# SparkFun_ACS712_Breakout.net
KiCad netlist of a schematic drawn in EAGLE
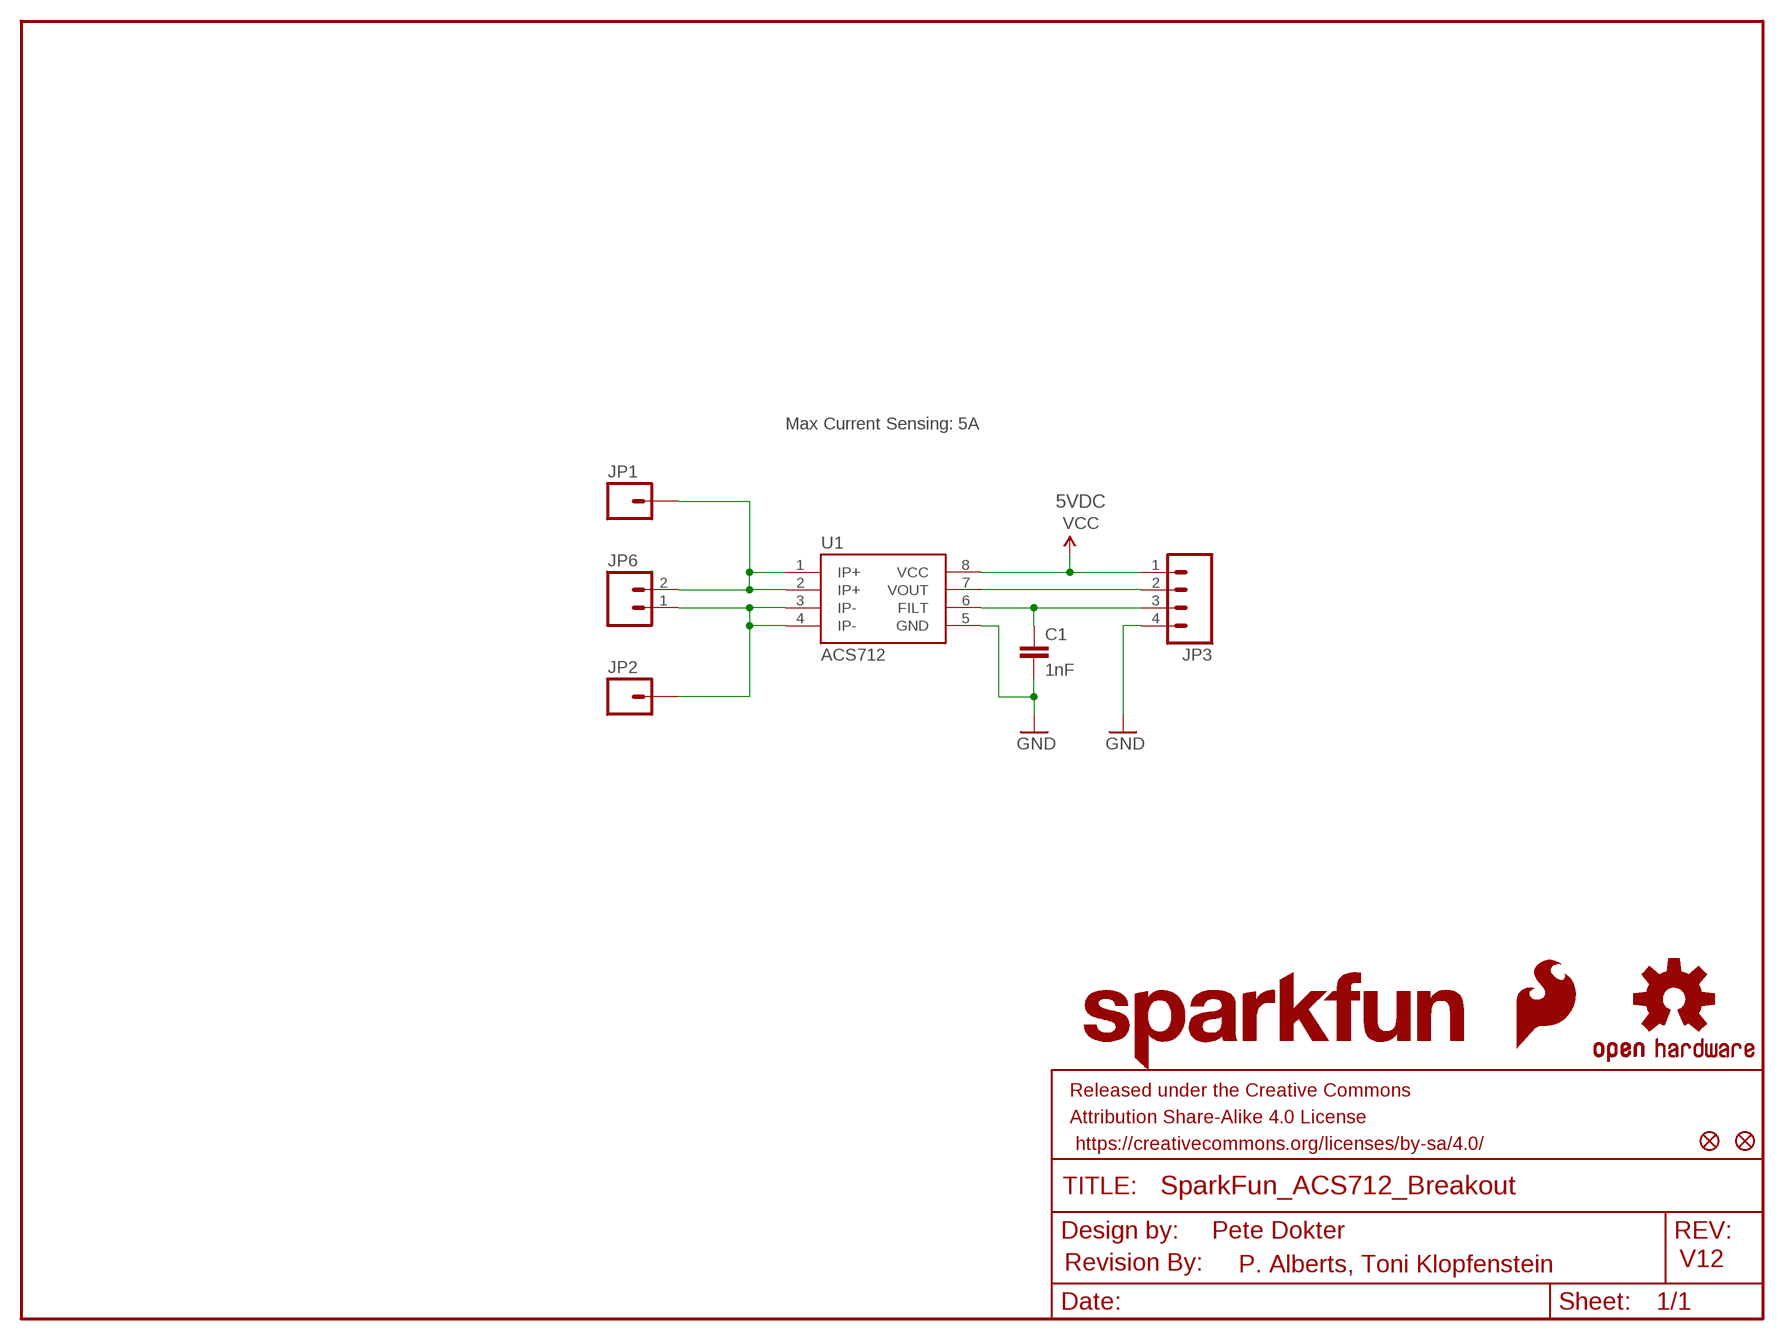
[diagram p0: schematic, sheet 1]

(export (version "E")
  (design (tool "Eeschema 10.0.6"))
  (components
    (comp (ref "C1")
      (value "1nF")
      (footprint "eagle-import:0603-CAP")
      (libsource (lib "eagle-import") (part "1NF/1000PF-50V-10%(0603)"))
    )
    (comp (ref "FRAME1")
      (value "FRAME-LETTER")
      (footprint "eagle-import:CREATIVE_COMMONS")
      (fields (field (name "DESIGNER") "NAME"))
      (libsource (lib "eagle-import") (part "FRAME-LETTER"))
    )
    (comp (ref "JP1")
      (value "M01-SMTSO-256-ET")
      (footprint "eagle-import:SMTSO-256-ET")
      (libsource (lib "eagle-import") (part "M01-SMTSO-256-ET"))
    )
    (comp (ref "JP2")
      (value "M01-SMTSO-256-ET")
      (footprint "eagle-import:SMTSO-256-ET")
      (libsource (lib "eagle-import") (part "M01-SMTSO-256-ET"))
    )
    (comp (ref "JP3")
      (value "M04PTH")
      (footprint "eagle-import:1X04")
      (libsource (lib "eagle-import") (part "M04PTH"))
    )
    (comp (ref "JP4")
      (value "FIDUCIALUFIDUCIAL")
      (footprint "eagle-import:MICRO-FIDUCIAL")
      (libsource (lib "eagle-import") (part "FIDUCIALUFIDUCIAL"))
    )
    (comp (ref "JP5")
      (value "FIDUCIALUFIDUCIAL")
      (footprint "eagle-import:MICRO-FIDUCIAL")
      (libsource (lib "eagle-import") (part "FIDUCIALUFIDUCIAL"))
    )
    (comp (ref "JP6")
      (value "M021X02_NO_SILK")
      (footprint "eagle-import:1X02_NO_SILK")
      (libsource (lib "eagle-import") (part "M021X02_NO_SILK"))
    )
    (comp (ref "LOGO1")
      (value "SFE_LOGO_NAME.1_INCH")
      (footprint "eagle-import:SFE_LOGO_NAME_.1")
      (libsource (lib "eagle-import") (part "SFE_LOGO_NAME.1_INCH"))
    )
    (comp (ref "LOGO2")
      (value "SFE_LOGO_FLAME.3_INCH")
      (footprint "eagle-import:SFE_LOGO_FLAME_.3")
      (libsource (lib "eagle-import") (part "SFE_LOGO_FLAME.3_INCH"))
    )
    (comp (ref "U$1")
      (value "REVISION")
      (footprint "eagle-import:REVISION")
      (libsource (lib "eagle-import") (part "REVISION"))
    )
    (comp (ref "U$3")
      (value "OSHW-LOGOS")
      (footprint "eagle-import:OSHW-LOGO-S")
      (libsource (lib "eagle-import") (part "OSHW-LOGOS"))
    )
    (comp (ref "U1")
      (value "ACS712")
      (footprint "eagle-import:SO08")
      (libsource (lib "eagle-import") (part "ACS712"))
    )
  )
  (nets
    (net (code "1") (name "GND") (class "Default")
      (node (ref "C1") (pin "2") (pinfunction "2_2") (pintype "passive"))
      (node (ref "JP3") (pin "4") (pinfunction "4_4") (pintype "passive"))
      (node (ref "U1") (pin "5") (pinfunction "GND_5") (pintype "bidirectional"))
    )
    (net (code "2") (name "Net-(JP1-1)") (class "Default")
      (node (ref "JP1") (pin "P$1") (pinfunction "1_P$1") (pintype "passive"))
      (node (ref "JP6") (pin "2") (pinfunction "2_2") (pintype "passive"))
      (node (ref "U1") (pin "1") (pinfunction "IP+_1") (pintype "bidirectional"))
      (node (ref "U1") (pin "2") (pinfunction "IP+_2") (pintype "bidirectional"))
    )
    (net (code "3") (name "Net-(JP2-1)") (class "Default")
      (node (ref "JP2") (pin "P$1") (pinfunction "1_P$1") (pintype "passive"))
      (node (ref "JP6") (pin "1") (pinfunction "1_1") (pintype "passive"))
      (node (ref "U1") (pin "3") (pinfunction "IP-_3") (pintype "bidirectional"))
      (node (ref "U1") (pin "4") (pinfunction "IP-_4") (pintype "bidirectional"))
    )
    (net (code "4") (name "Net-(U1-FILT)") (class "Default")
      (node (ref "C1") (pin "1") (pinfunction "1_1") (pintype "passive"))
      (node (ref "JP3") (pin "3") (pinfunction "3_3") (pintype "passive"))
      (node (ref "U1") (pin "6") (pinfunction "FILT_6") (pintype "bidirectional"))
    )
    (net (code "5") (name "Net-(U1-VOUT)") (class "Default")
      (node (ref "JP3") (pin "2") (pinfunction "2_2") (pintype "passive"))
      (node (ref "U1") (pin "7") (pinfunction "VOUT_7") (pintype "bidirectional"))
    )
    (net (code "6") (name "VCC") (class "Default")
      (node (ref "JP3") (pin "1") (pinfunction "1_1") (pintype "passive"))
      (node (ref "U1") (pin "8") (pinfunction "VCC_8") (pintype "bidirectional"))
    )
  )
)
